# Sch.net
KiCad netlist of a schematic drawn in EAGLE
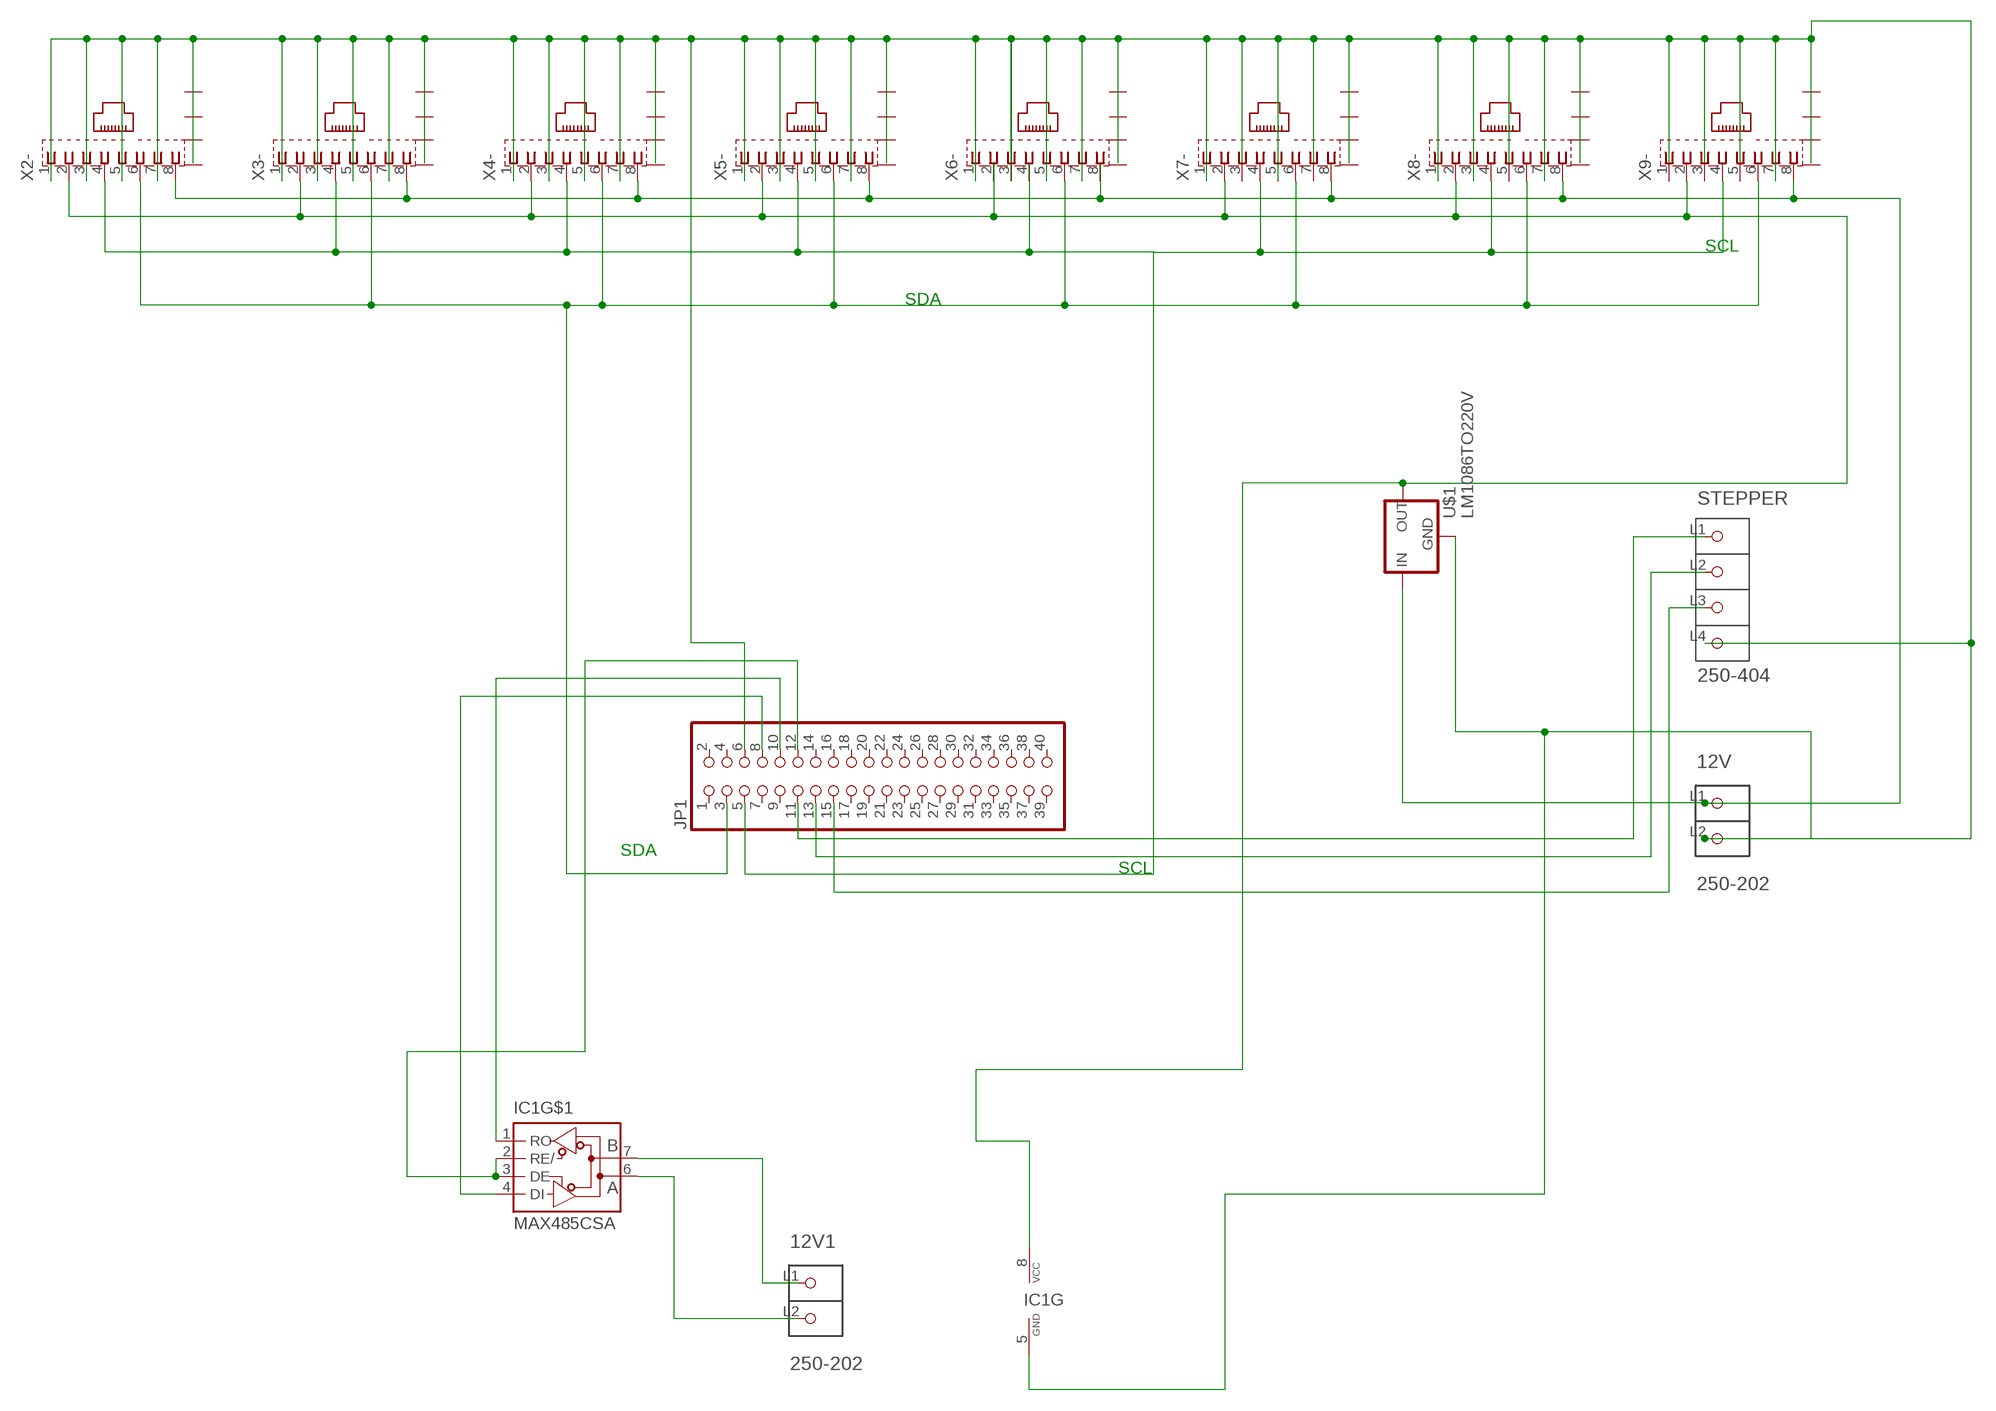
[diagram p0: schematic, sheet 1]

(export (version "E")
  (design (tool "Eeschema 10.0.6"))
  (components
    (comp (ref "12V")
      (value "250-202")
      (footprint "eagle-import:P-250-202")
      (libsource (lib "eagle-import") (part "250-202"))
    )
    (comp (ref "12V1")
      (value "250-202")
      (footprint "eagle-import:P-250-202")
      (libsource (lib "eagle-import") (part "250-202"))
    )
    (comp (ref "IC1")
      (value "MAX485CSA")
      (footprint "eagle-import:SO08")
      (libsource (lib "eagle-import") (part "MAX485CSA"))
    )
    (comp (ref "JP1")
      (value "PINHD-2X20_2.54")
      (footprint "eagle-import:2X20")
      (libsource (lib "eagle-import") (part "PINHD-2X20_2.54"))
    )
    (comp (ref "STEPPER")
      (value "250-404")
      (footprint "eagle-import:P-250-404")
      (libsource (lib "eagle-import") (part "250-404"))
    )
    (comp (ref "U$1")
      (value "LM1086TO220V")
      (footprint "eagle-import:TO220S")
      (libsource (lib "eagle-import") (part "LM1086TO220V"))
    )
    (comp (ref "X2")
      (value "RJ45")
      (footprint "eagle-import:RJ45")
      (libsource (lib "eagle-import") (part "RJ45"))
    )
    (comp (ref "X3")
      (value "RJ45")
      (footprint "eagle-import:RJ45")
      (libsource (lib "eagle-import") (part "RJ45"))
    )
    (comp (ref "X4")
      (value "RJ45")
      (footprint "eagle-import:RJ45")
      (libsource (lib "eagle-import") (part "RJ45"))
    )
    (comp (ref "X5")
      (value "RJ45")
      (footprint "eagle-import:RJ45")
      (libsource (lib "eagle-import") (part "RJ45"))
    )
    (comp (ref "X6")
      (value "RJ45")
      (footprint "eagle-import:RJ45")
      (libsource (lib "eagle-import") (part "RJ45"))
    )
    (comp (ref "X7")
      (value "RJ45")
      (footprint "eagle-import:RJ45")
      (libsource (lib "eagle-import") (part "RJ45"))
    )
    (comp (ref "X8")
      (value "RJ45")
      (footprint "eagle-import:RJ45")
      (libsource (lib "eagle-import") (part "RJ45"))
    )
    (comp (ref "X9")
      (value "RJ45")
      (footprint "eagle-import:RJ45")
      (libsource (lib "eagle-import") (part "RJ45"))
    )
  )
  (nets
    (net (code "1") (name "Net-(12V-P1)") (class "Default")
      (node (ref "12V") (pin "L1") (pinfunction "P1_L1") (pintype "bidirectional"))
      (node (ref "U$1") (pin "3") (pinfunction "IN_3") (pintype "input"))
      (node (ref "X2") (pin "8") (pinfunction "8_8") (pintype "passive"))
      (node (ref "X3") (pin "8") (pinfunction "8_8") (pintype "passive"))
      (node (ref "X4") (pin "8") (pinfunction "8_8") (pintype "passive"))
      (node (ref "X5") (pin "8") (pinfunction "8_8") (pintype "passive"))
      (node (ref "X6") (pin "8") (pinfunction "8_8") (pintype "passive"))
      (node (ref "X7") (pin "8") (pinfunction "8_8") (pintype "passive"))
      (node (ref "X8") (pin "8") (pinfunction "8_8") (pintype "passive"))
      (node (ref "X9") (pin "8") (pinfunction "8_8") (pintype "passive"))
    )
    (net (code "2") (name "Net-(12V-P2)") (class "Default")
      (node (ref "12V") (pin "L2") (pinfunction "P2_L2") (pintype "bidirectional"))
      (node (ref "IC1") (pin "5") (pinfunction "GND_5") (pintype "power_in"))
      (node (ref "JP1") (pin "6") (pinfunction "6_6") (pintype "passive"))
      (node (ref "STEPPER") (pin "L4") (pinfunction "P4_L4") (pintype "bidirectional"))
      (node (ref "U$1") (pin "1") (pinfunction "GND_1") (pintype "input"))
      (node (ref "X2") (pin "1") (pinfunction "1_1") (pintype "passive"))
      (node (ref "X2") (pin "3") (pinfunction "3_3") (pintype "passive"))
      (node (ref "X2") (pin "5") (pinfunction "5_5") (pintype "passive"))
      (node (ref "X2") (pin "7") (pinfunction "7_7") (pintype "passive"))
      (node (ref "X3") (pin "1") (pinfunction "1_1") (pintype "passive"))
      (node (ref "X3") (pin "3") (pinfunction "3_3") (pintype "passive"))
      (node (ref "X3") (pin "5") (pinfunction "5_5") (pintype "passive"))
      (node (ref "X3") (pin "7") (pinfunction "7_7") (pintype "passive"))
      (node (ref "X4") (pin "1") (pinfunction "1_1") (pintype "passive"))
      (node (ref "X4") (pin "3") (pinfunction "3_3") (pintype "passive"))
      (node (ref "X4") (pin "5") (pinfunction "5_5") (pintype "passive"))
      (node (ref "X4") (pin "7") (pinfunction "7_7") (pintype "passive"))
      (node (ref "X5") (pin "1") (pinfunction "1_1") (pintype "passive"))
      (node (ref "X5") (pin "3") (pinfunction "3_3") (pintype "passive"))
      (node (ref "X5") (pin "5") (pinfunction "5_5") (pintype "passive"))
      (node (ref "X5") (pin "7") (pinfunction "7_7") (pintype "passive"))
      (node (ref "X6") (pin "1") (pinfunction "1_1") (pintype "passive"))
      (node (ref "X6") (pin "3") (pinfunction "3_3") (pintype "passive"))
      (node (ref "X6") (pin "5") (pinfunction "5_5") (pintype "passive"))
      (node (ref "X6") (pin "7") (pinfunction "7_7") (pintype "passive"))
      (node (ref "X7") (pin "1") (pinfunction "1_1") (pintype "passive"))
      (node (ref "X8") (pin "1") (pinfunction "1_1") (pintype "passive"))
      (node (ref "X8") (pin "3") (pinfunction "3_3") (pintype "passive"))
      (node (ref "X8") (pin "7") (pinfunction "7_7") (pintype "passive"))
      (node (ref "X9") (pin "7") (pinfunction "7_7") (pintype "passive"))
    )
    (net (code "3") (name "Net-(12V1-P1)") (class "Default")
      (node (ref "12V1") (pin "L1") (pinfunction "P1_L1") (pintype "bidirectional"))
      (node (ref "IC1") (pin "7") (pinfunction "B_7") (pintype "passive"))
    )
    (net (code "4") (name "Net-(12V1-P2)") (class "Default")
      (node (ref "12V1") (pin "L2") (pinfunction "P2_L2") (pintype "bidirectional"))
      (node (ref "IC1") (pin "6") (pinfunction "A_6") (pintype "passive"))
    )
    (net (code "5") (name "Net-(IC1A-VCC)") (class "Default")
      (node (ref "IC1") (pin "8") (pinfunction "VCC_8") (pintype "power_in"))
      (node (ref "U$1") (pin "2") (pinfunction "OUT_2") (pintype "passive"))
      (node (ref "X2") (pin "2") (pinfunction "2_2") (pintype "passive"))
      (node (ref "X3") (pin "2") (pinfunction "2_2") (pintype "passive"))
      (node (ref "X4") (pin "2") (pinfunction "2_2") (pintype "passive"))
      (node (ref "X5") (pin "2") (pinfunction "2_2") (pintype "passive"))
      (node (ref "X6") (pin "2") (pinfunction "2_2") (pintype "passive"))
      (node (ref "X7") (pin "2") (pinfunction "2_2") (pintype "passive"))
      (node (ref "X8") (pin "2") (pinfunction "2_2") (pintype "passive"))
      (node (ref "X9") (pin "2") (pinfunction "2_2") (pintype "passive"))
    )
    (net (code "6") (name "Net-(IC1B-DE)") (class "Default")
      (node (ref "IC1") (pin "2") (pinfunction "RE/_2") (pintype "input"))
      (node (ref "IC1") (pin "3") (pinfunction "DE_3") (pintype "input"))
      (node (ref "JP1") (pin "12") (pinfunction "12_12") (pintype "passive"))
    )
    (net (code "7") (name "Net-(IC1B-DI)") (class "Default")
      (node (ref "IC1") (pin "4") (pinfunction "DI_4") (pintype "input"))
      (node (ref "JP1") (pin "8") (pinfunction "8_8") (pintype "passive"))
    )
    (net (code "8") (name "Net-(IC1B-RO)") (class "Default")
      (node (ref "IC1") (pin "1") (pinfunction "RO_1") (pintype "output"))
      (node (ref "JP1") (pin "10") (pinfunction "10_10") (pintype "passive"))
    )
    (net (code "9") (name "Net-(JP1-Pad3)") (class "Default")
      (node (ref "JP1") (pin "3") (pinfunction "3_3") (pintype "passive"))
      (node (ref "X2") (pin "6") (pinfunction "6_6") (pintype "passive"))
      (node (ref "X3") (pin "6") (pinfunction "6_6") (pintype "passive"))
      (node (ref "X4") (pin "6") (pinfunction "6_6") (pintype "passive"))
      (node (ref "X5") (pin "6") (pinfunction "6_6") (pintype "passive"))
      (node (ref "X6") (pin "6") (pinfunction "6_6") (pintype "passive"))
      (node (ref "X7") (pin "6") (pinfunction "6_6") (pintype "passive"))
      (node (ref "X8") (pin "6") (pinfunction "6_6") (pintype "passive"))
      (node (ref "X9") (pin "6") (pinfunction "6_6") (pintype "passive"))
    )
    (net (code "10") (name "Net-(JP1-Pad5)") (class "Default")
      (node (ref "JP1") (pin "5") (pinfunction "5_5") (pintype "passive"))
      (node (ref "X2") (pin "4") (pinfunction "4_4") (pintype "passive"))
      (node (ref "X3") (pin "4") (pinfunction "4_4") (pintype "passive"))
      (node (ref "X4") (pin "4") (pinfunction "4_4") (pintype "passive"))
      (node (ref "X5") (pin "4") (pinfunction "4_4") (pintype "passive"))
      (node (ref "X6") (pin "4") (pinfunction "4_4") (pintype "passive"))
      (node (ref "X7") (pin "4") (pinfunction "4_4") (pintype "passive"))
      (node (ref "X8") (pin "4") (pinfunction "4_4") (pintype "passive"))
      (node (ref "X9") (pin "4") (pinfunction "4_4") (pintype "passive"))
    )
    (net (code "11") (name "Net-(STEPPER-P1)") (class "Default")
      (node (ref "JP1") (pin "11") (pinfunction "11_11") (pintype "passive"))
      (node (ref "STEPPER") (pin "L1") (pinfunction "P1_L1") (pintype "bidirectional"))
    )
    (net (code "12") (name "Net-(STEPPER-P2)") (class "Default")
      (node (ref "JP1") (pin "13") (pinfunction "13_13") (pintype "passive"))
      (node (ref "STEPPER") (pin "L2") (pinfunction "P2_L2") (pintype "bidirectional"))
    )
    (net (code "13") (name "Net-(STEPPER-P3)") (class "Default")
      (node (ref "JP1") (pin "15") (pinfunction "15_15") (pintype "passive"))
      (node (ref "STEPPER") (pin "L3") (pinfunction "P3_L3") (pintype "bidirectional"))
    )
    (net (code "14") (name "unconnected-(JP1-Pad1)") (class "Default")
      (node (ref "JP1") (pin "1") (pinfunction "1_1") (pintype "passive"))
    )
    (net (code "15") (name "unconnected-(JP1-Pad2)") (class "Default")
      (node (ref "JP1") (pin "2") (pinfunction "2_2") (pintype "passive"))
    )
    (net (code "16") (name "unconnected-(JP1-Pad4)") (class "Default")
      (node (ref "JP1") (pin "4") (pinfunction "4_4") (pintype "passive"))
    )
    (net (code "17") (name "unconnected-(JP1-Pad7)") (class "Default")
      (node (ref "JP1") (pin "7") (pinfunction "7_7") (pintype "passive"))
    )
    (net (code "18") (name "unconnected-(JP1-Pad9)") (class "Default")
      (node (ref "JP1") (pin "9") (pinfunction "9_9") (pintype "passive"))
    )
    (net (code "19") (name "unconnected-(JP1-Pad14)") (class "Default")
      (node (ref "JP1") (pin "14") (pinfunction "14_14") (pintype "passive"))
    )
    (net (code "20") (name "unconnected-(JP1-Pad16)") (class "Default")
      (node (ref "JP1") (pin "16") (pinfunction "16_16") (pintype "passive"))
    )
    (net (code "21") (name "unconnected-(JP1-Pad17)") (class "Default")
      (node (ref "JP1") (pin "17") (pinfunction "17_17") (pintype "passive"))
    )
    (net (code "22") (name "unconnected-(JP1-Pad18)") (class "Default")
      (node (ref "JP1") (pin "18") (pinfunction "18_18") (pintype "passive"))
    )
    (net (code "23") (name "unconnected-(JP1-Pad19)") (class "Default")
      (node (ref "JP1") (pin "19") (pinfunction "19_19") (pintype "passive"))
    )
    (net (code "24") (name "unconnected-(JP1-Pad20)") (class "Default")
      (node (ref "JP1") (pin "20") (pinfunction "20_20") (pintype "passive"))
    )
    (net (code "25") (name "unconnected-(JP1-Pad21)") (class "Default")
      (node (ref "JP1") (pin "21") (pinfunction "21_21") (pintype "passive"))
    )
    (net (code "26") (name "unconnected-(JP1-Pad22)") (class "Default")
      (node (ref "JP1") (pin "22") (pinfunction "22_22") (pintype "passive"))
    )
    (net (code "27") (name "unconnected-(JP1-Pad23)") (class "Default")
      (node (ref "JP1") (pin "23") (pinfunction "23_23") (pintype "passive"))
    )
    (net (code "28") (name "unconnected-(JP1-Pad24)") (class "Default")
      (node (ref "JP1") (pin "24") (pinfunction "24_24") (pintype "passive"))
    )
    (net (code "29") (name "unconnected-(JP1-Pad25)") (class "Default")
      (node (ref "JP1") (pin "25") (pinfunction "25_25") (pintype "passive"))
    )
    (net (code "30") (name "unconnected-(JP1-Pad26)") (class "Default")
      (node (ref "JP1") (pin "26") (pinfunction "26_26") (pintype "passive"))
    )
    (net (code "31") (name "unconnected-(JP1-Pad27)") (class "Default")
      (node (ref "JP1") (pin "27") (pinfunction "27_27") (pintype "passive"))
    )
    (net (code "32") (name "unconnected-(JP1-Pad28)") (class "Default")
      (node (ref "JP1") (pin "28") (pinfunction "28_28") (pintype "passive"))
    )
    (net (code "33") (name "unconnected-(JP1-Pad29)") (class "Default")
      (node (ref "JP1") (pin "29") (pinfunction "29_29") (pintype "passive"))
    )
    (net (code "34") (name "unconnected-(JP1-Pad30)") (class "Default")
      (node (ref "JP1") (pin "30") (pinfunction "30_30") (pintype "passive"))
    )
    (net (code "35") (name "unconnected-(JP1-Pad31)") (class "Default")
      (node (ref "JP1") (pin "31") (pinfunction "31_31") (pintype "passive"))
    )
    (net (code "36") (name "unconnected-(JP1-Pad32)") (class "Default")
      (node (ref "JP1") (pin "32") (pinfunction "32_32") (pintype "passive"))
    )
    (net (code "37") (name "unconnected-(JP1-Pad33)") (class "Default")
      (node (ref "JP1") (pin "33") (pinfunction "33_33") (pintype "passive"))
    )
    (net (code "38") (name "unconnected-(JP1-Pad34)") (class "Default")
      (node (ref "JP1") (pin "34") (pinfunction "34_34") (pintype "passive"))
    )
    (net (code "39") (name "unconnected-(JP1-Pad35)") (class "Default")
      (node (ref "JP1") (pin "35") (pinfunction "35_35") (pintype "passive"))
    )
    (net (code "40") (name "unconnected-(JP1-Pad36)") (class "Default")
      (node (ref "JP1") (pin "36") (pinfunction "36_36") (pintype "passive"))
    )
    (net (code "41") (name "unconnected-(JP1-Pad37)") (class "Default")
      (node (ref "JP1") (pin "37") (pinfunction "37_37") (pintype "passive"))
    )
    (net (code "42") (name "unconnected-(JP1-Pad38)") (class "Default")
      (node (ref "JP1") (pin "38") (pinfunction "38_38") (pintype "passive"))
    )
    (net (code "43") (name "unconnected-(JP1-Pad39)") (class "Default")
      (node (ref "JP1") (pin "39") (pinfunction "39_39") (pintype "passive"))
    )
    (net (code "44") (name "unconnected-(JP1-Pad40)") (class "Default")
      (node (ref "JP1") (pin "40") (pinfunction "40_40") (pintype "passive"))
    )
    (net (code "45") (name "unconnected-(X2B-1-PadG1)") (class "Default")
      (node (ref "X2") (pin "G1") (pinfunction "1_G1") (pintype "passive"))
    )
    (net (code "46") (name "unconnected-(X2C-1-PadG2)") (class "Default")
      (node (ref "X2") (pin "G2") (pinfunction "1_G2") (pintype "passive"))
    )
    (net (code "47") (name "unconnected-(X2D-1-PadG3)") (class "Default")
      (node (ref "X2") (pin "G3") (pinfunction "1_G3") (pintype "passive"))
    )
    (net (code "48") (name "unconnected-(X2E-1-PadG4)") (class "Default")
      (node (ref "X2") (pin "G4") (pinfunction "1_G4") (pintype "passive"))
    )
    (net (code "49") (name "unconnected-(X3B-1-PadG1)") (class "Default")
      (node (ref "X3") (pin "G1") (pinfunction "1_G1") (pintype "passive"))
    )
    (net (code "50") (name "unconnected-(X3C-1-PadG2)") (class "Default")
      (node (ref "X3") (pin "G2") (pinfunction "1_G2") (pintype "passive"))
    )
    (net (code "51") (name "unconnected-(X3D-1-PadG3)") (class "Default")
      (node (ref "X3") (pin "G3") (pinfunction "1_G3") (pintype "passive"))
    )
    (net (code "52") (name "unconnected-(X3E-1-PadG4)") (class "Default")
      (node (ref "X3") (pin "G4") (pinfunction "1_G4") (pintype "passive"))
    )
    (net (code "53") (name "unconnected-(X4B-1-PadG1)") (class "Default")
      (node (ref "X4") (pin "G1") (pinfunction "1_G1") (pintype "passive"))
    )
    (net (code "54") (name "unconnected-(X4C-1-PadG2)") (class "Default")
      (node (ref "X4") (pin "G2") (pinfunction "1_G2") (pintype "passive"))
    )
    (net (code "55") (name "unconnected-(X4D-1-PadG3)") (class "Default")
      (node (ref "X4") (pin "G3") (pinfunction "1_G3") (pintype "passive"))
    )
    (net (code "56") (name "unconnected-(X4E-1-PadG4)") (class "Default")
      (node (ref "X4") (pin "G4") (pinfunction "1_G4") (pintype "passive"))
    )
    (net (code "57") (name "unconnected-(X5B-1-PadG1)") (class "Default")
      (node (ref "X5") (pin "G1") (pinfunction "1_G1") (pintype "passive"))
    )
    (net (code "58") (name "unconnected-(X5C-1-PadG2)") (class "Default")
      (node (ref "X5") (pin "G2") (pinfunction "1_G2") (pintype "passive"))
    )
    (net (code "59") (name "unconnected-(X5D-1-PadG3)") (class "Default")
      (node (ref "X5") (pin "G3") (pinfunction "1_G3") (pintype "passive"))
    )
    (net (code "60") (name "unconnected-(X5E-1-PadG4)") (class "Default")
      (node (ref "X5") (pin "G4") (pinfunction "1_G4") (pintype "passive"))
    )
    (net (code "61") (name "unconnected-(X6B-1-PadG1)") (class "Default")
      (node (ref "X6") (pin "G1") (pinfunction "1_G1") (pintype "passive"))
    )
    (net (code "62") (name "unconnected-(X6C-1-PadG2)") (class "Default")
      (node (ref "X6") (pin "G2") (pinfunction "1_G2") (pintype "passive"))
    )
    (net (code "63") (name "unconnected-(X6D-1-PadG3)") (class "Default")
      (node (ref "X6") (pin "G3") (pinfunction "1_G3") (pintype "passive"))
    )
    (net (code "64") (name "unconnected-(X6E-1-PadG4)") (class "Default")
      (node (ref "X6") (pin "G4") (pinfunction "1_G4") (pintype "passive"))
    )
    (net (code "65") (name "unconnected-(X7-Pad3)") (class "Default")
      (node (ref "X7") (pin "3") (pinfunction "3_3") (pintype "passive"))
    )
    (net (code "66") (name "unconnected-(X7-Pad5)") (class "Default")
      (node (ref "X7") (pin "5") (pinfunction "5_5") (pintype "passive"))
    )
    (net (code "67") (name "unconnected-(X7-Pad7)") (class "Default")
      (node (ref "X7") (pin "7") (pinfunction "7_7") (pintype "passive"))
    )
    (net (code "68") (name "unconnected-(X7B-1-PadG1)") (class "Default")
      (node (ref "X7") (pin "G1") (pinfunction "1_G1") (pintype "passive"))
    )
    (net (code "69") (name "unconnected-(X7C-1-PadG2)") (class "Default")
      (node (ref "X7") (pin "G2") (pinfunction "1_G2") (pintype "passive"))
    )
    (net (code "70") (name "unconnected-(X7D-1-PadG3)") (class "Default")
      (node (ref "X7") (pin "G3") (pinfunction "1_G3") (pintype "passive"))
    )
    (net (code "71") (name "unconnected-(X7E-1-PadG4)") (class "Default")
      (node (ref "X7") (pin "G4") (pinfunction "1_G4") (pintype "passive"))
    )
    (net (code "72") (name "unconnected-(X8-Pad5)") (class "Default")
      (node (ref "X8") (pin "5") (pinfunction "5_5") (pintype "passive"))
    )
    (net (code "73") (name "unconnected-(X8B-1-PadG1)") (class "Default")
      (node (ref "X8") (pin "G1") (pinfunction "1_G1") (pintype "passive"))
    )
    (net (code "74") (name "unconnected-(X8C-1-PadG2)") (class "Default")
      (node (ref "X8") (pin "G2") (pinfunction "1_G2") (pintype "passive"))
    )
    (net (code "75") (name "unconnected-(X8D-1-PadG3)") (class "Default")
      (node (ref "X8") (pin "G3") (pinfunction "1_G3") (pintype "passive"))
    )
    (net (code "76") (name "unconnected-(X8E-1-PadG4)") (class "Default")
      (node (ref "X8") (pin "G4") (pinfunction "1_G4") (pintype "passive"))
    )
    (net (code "77") (name "unconnected-(X9-Pad1)") (class "Default")
      (node (ref "X9") (pin "1") (pinfunction "1_1") (pintype "passive"))
    )
    (net (code "78") (name "unconnected-(X9-Pad3)") (class "Default")
      (node (ref "X9") (pin "3") (pinfunction "3_3") (pintype "passive"))
    )
    (net (code "79") (name "unconnected-(X9-Pad5)") (class "Default")
      (node (ref "X9") (pin "5") (pinfunction "5_5") (pintype "passive"))
    )
    (net (code "80") (name "unconnected-(X9B-1-PadG1)") (class "Default")
      (node (ref "X9") (pin "G1") (pinfunction "1_G1") (pintype "passive"))
    )
    (net (code "81") (name "unconnected-(X9C-1-PadG2)") (class "Default")
      (node (ref "X9") (pin "G2") (pinfunction "1_G2") (pintype "passive"))
    )
    (net (code "82") (name "unconnected-(X9D-1-PadG3)") (class "Default")
      (node (ref "X9") (pin "G3") (pinfunction "1_G3") (pintype "passive"))
    )
    (net (code "83") (name "unconnected-(X9E-1-PadG4)") (class "Default")
      (node (ref "X9") (pin "G4") (pinfunction "1_G4") (pintype "passive"))
    )
  )
)
